# AirU_v2_0_wPOE.net
KiCad netlist of a schematic drawn in EAGLE
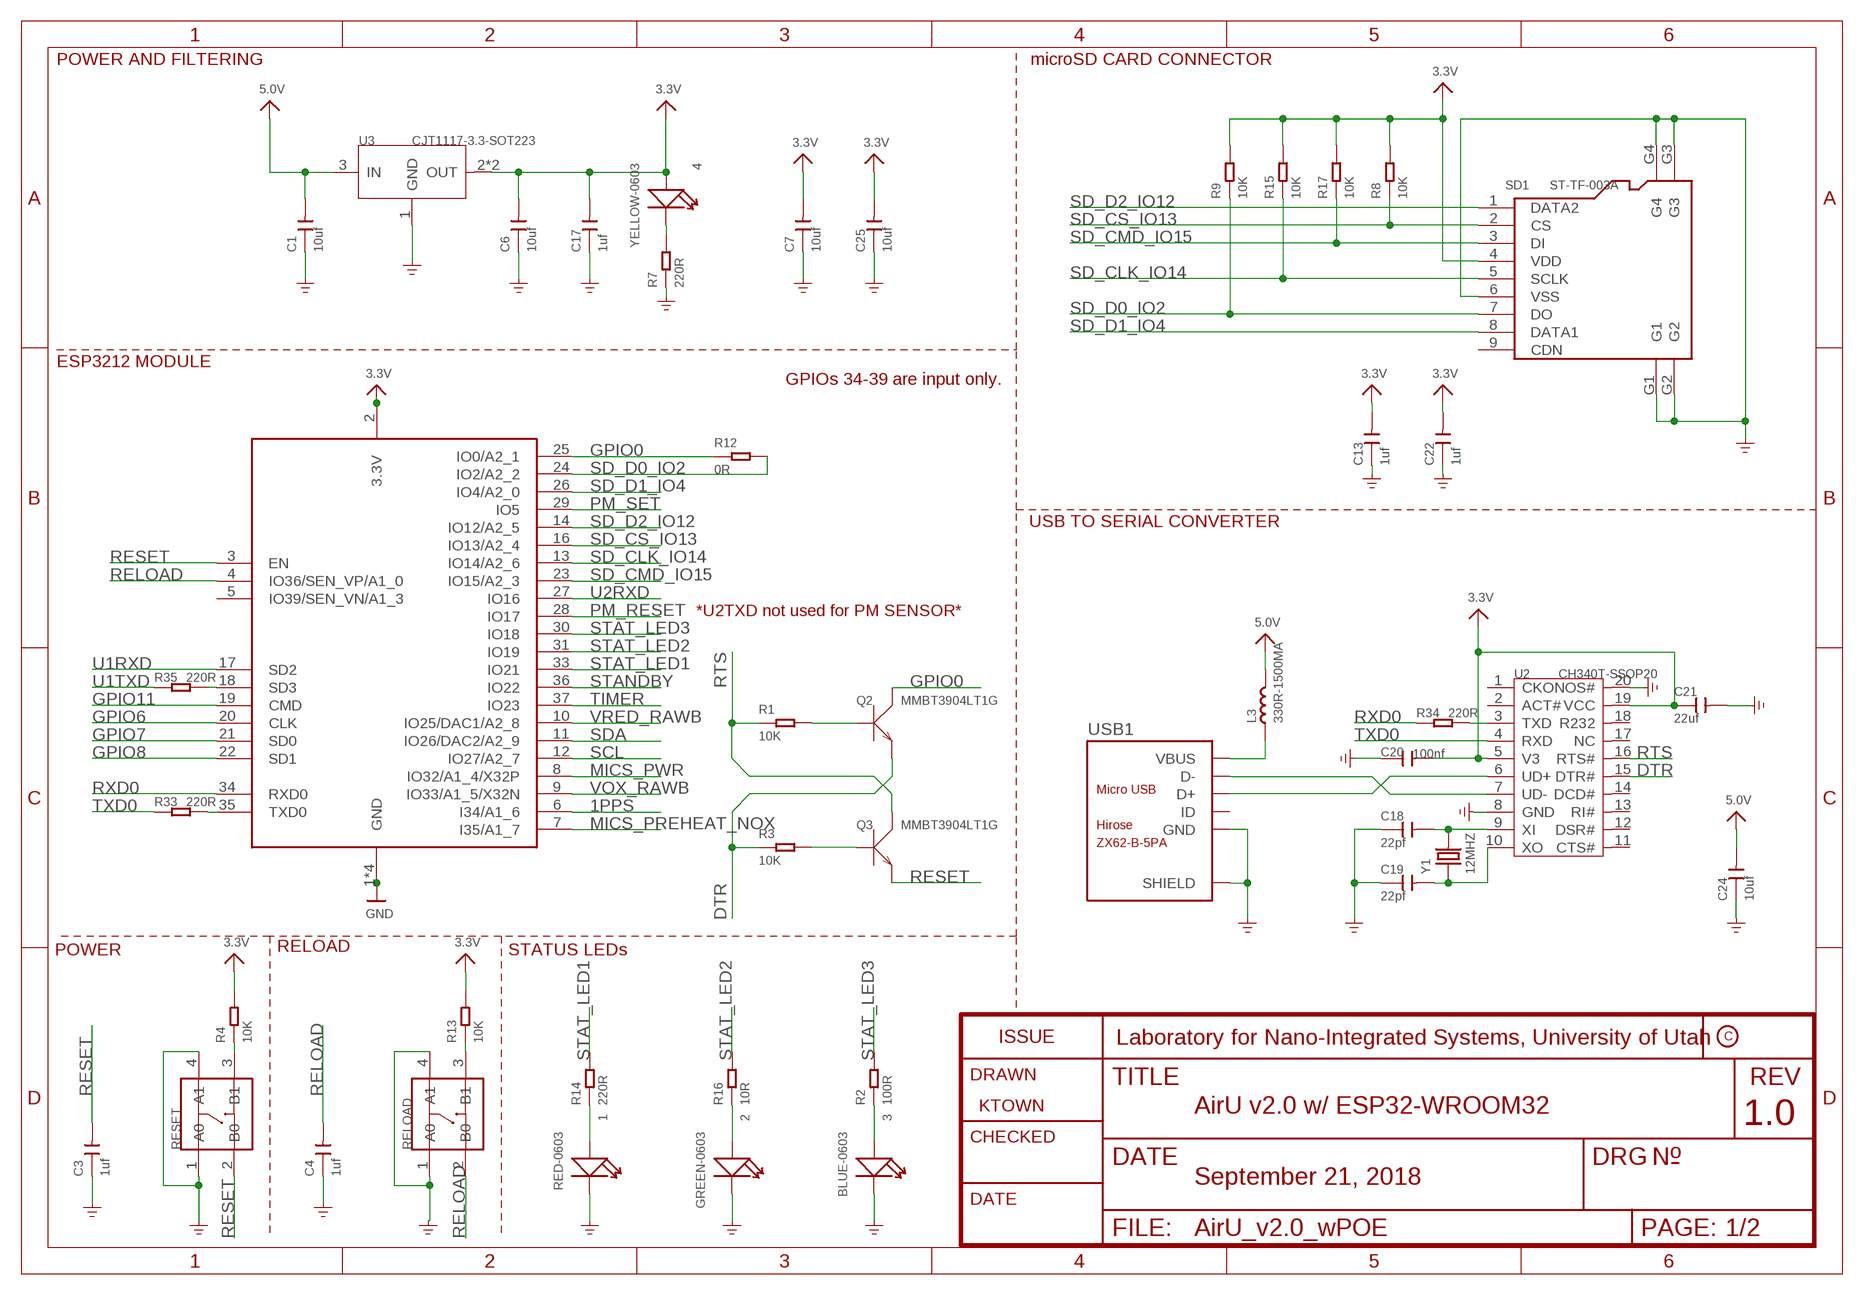
[diagram p0: schematic, sheet 1]
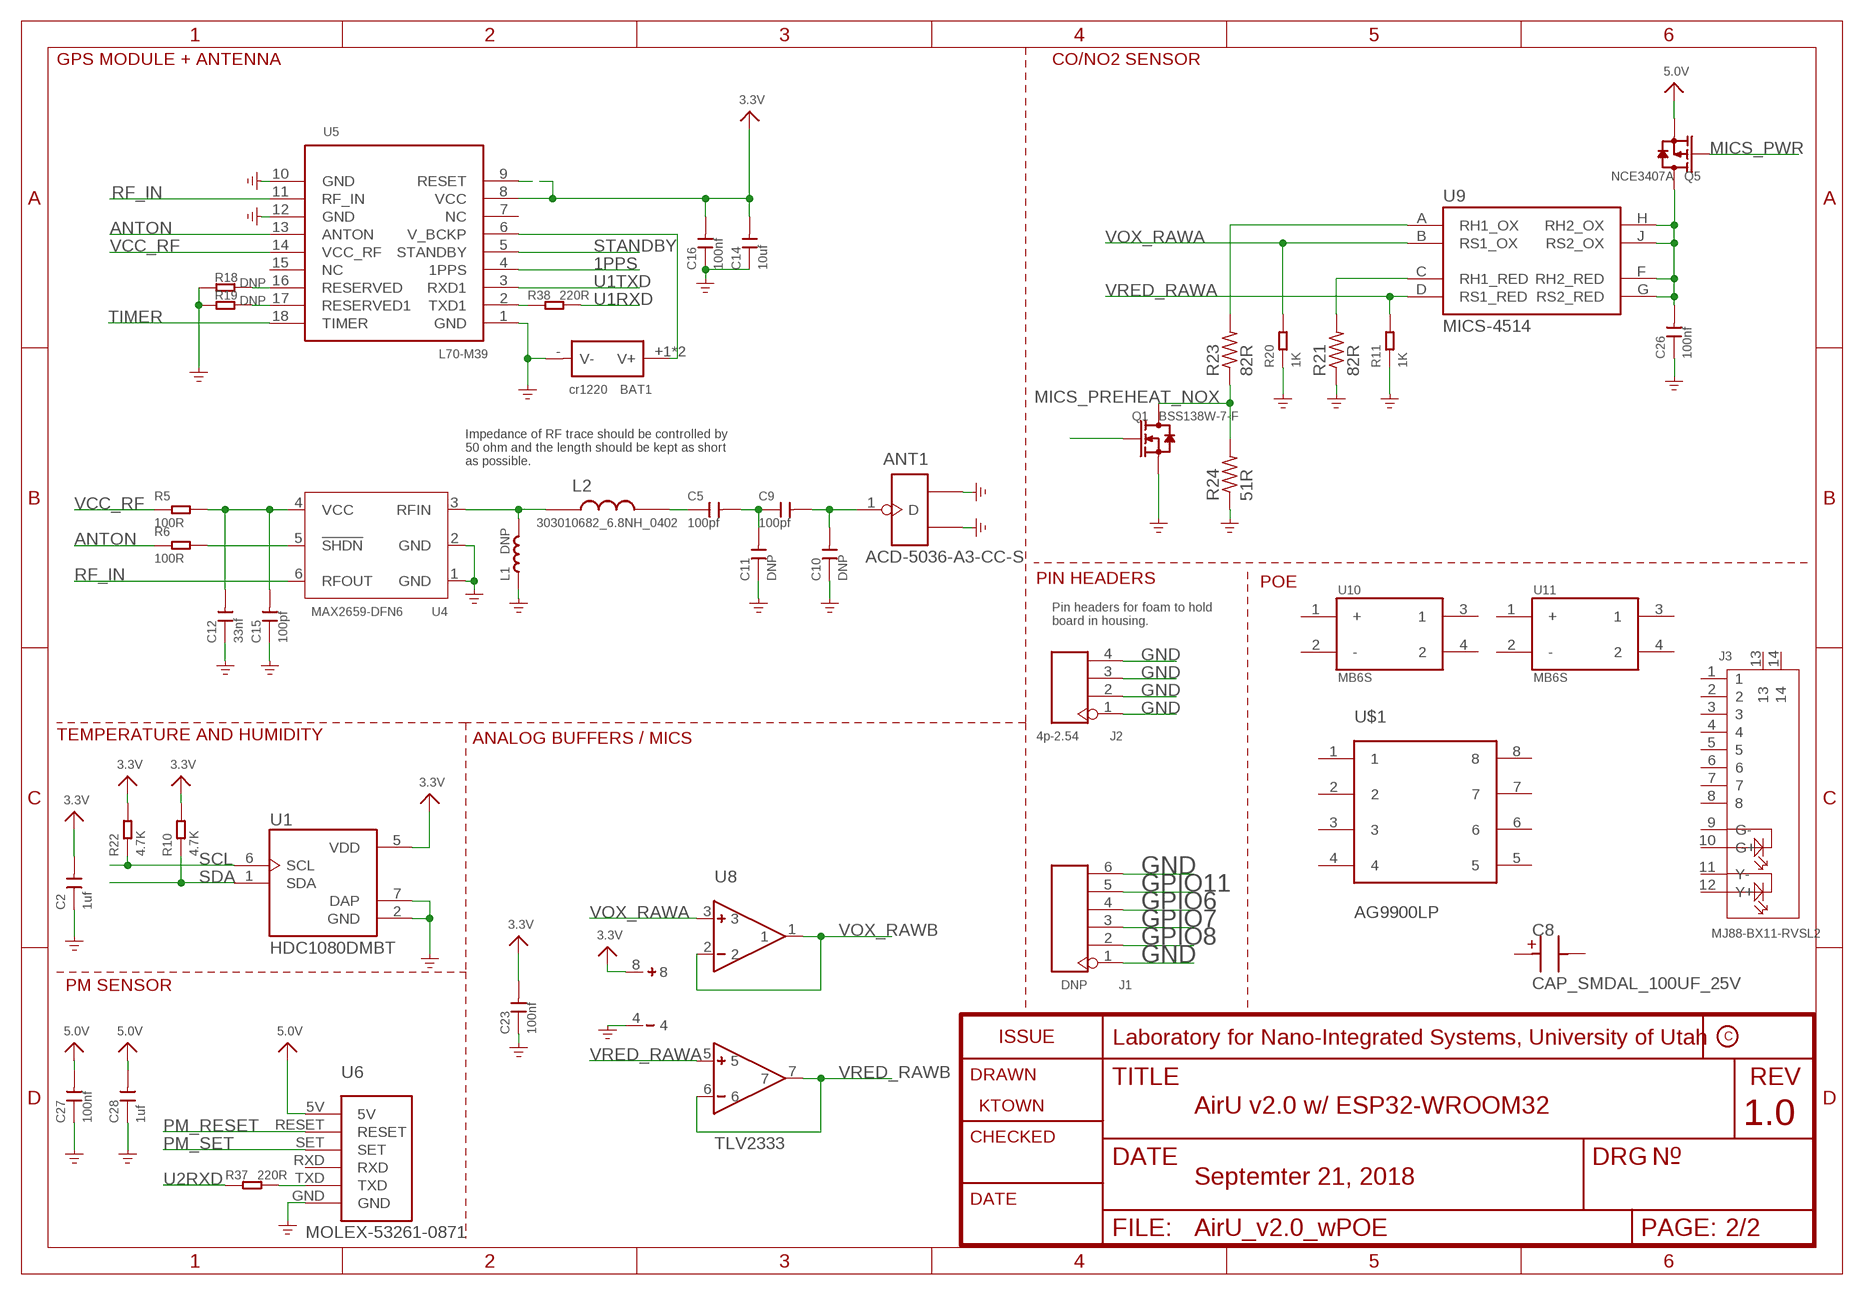
[diagram p1: schematic, sheet 2]

(export (version "E")
  (design (tool "Eeschema 10.0.6"))
  (components
    (comp (ref "1")
      (value "RED-0603")
      (footprint "eagle-import:LED-0603")
      (fields (field (name "MPN") "19-217-R6C-AL1M2VY-3T"))
      (libsource (lib "eagle-import") (part "LED-SMD-RED-DIFFUSED(0603)"))
    )
    (comp (ref "2")
      (value "GREEN-0603")
      (footprint "eagle-import:LED-0603")
      (fields (field (name "MPN") "19-217-G7C-AN1P2-3T"))
      (libsource (lib "eagle-import") (part "SMD-LED-CLEAR-GREEN(0603)"))
    )
    (comp (ref "3")
      (value "BLUE-0603")
      (footprint "eagle-import:LED-0603")
      (fields (field (name "MPN") "19-217-BHC-ZL1M2RY-3T"))
      (libsource (lib "eagle-import") (part "SMD-LED-CLEAR-BLUE(0603)"))
    )
    (comp (ref "4")
      (value "YELLOW-0603")
      (footprint "eagle-import:LED-0603")
      (fields (field (name "MPN") "19-217-Y5C-AM1N1VY-3T"))
      (libsource (lib "eagle-import") (part "SMD-LED-CLEAR-YELLOW(0603)"))
    )
    (comp (ref "C1")
      (value "10uf")
      (footprint "eagle-import:C0603")
      (fields (field (name "MPN") "CC0603KRX5R6BB106"))
      (libsource (lib "eagle-import") (part "CERAMIC-10UF-10V-10%-X5R(0603)"))
    )
    (comp (ref "C3")
      (value "1uf")
      (footprint "eagle-import:C0603")
      (fields (field (name "MPN") "CC0603KRX7R8BB105"))
      (libsource (lib "eagle-import") (part "CERAMIC-1UF-25V-10%-X7R(0603)"))
    )
    (comp (ref "C4")
      (value "1uf")
      (footprint "eagle-import:C0603")
      (fields (field (name "MPN") "CC0603KRX7R8BB105"))
      (libsource (lib "eagle-import") (part "CERAMIC-1UF-25V-10%-X7R(0603)"))
    )
    (comp (ref "C6")
      (value "10uf")
      (footprint "eagle-import:C0603")
      (fields (field (name "MPN") "CC0603KRX5R6BB106"))
      (libsource (lib "eagle-import") (part "CERAMIC-10UF-10V-10%-X5R(0603)"))
    )
    (comp (ref "C7")
      (value "10uf")
      (footprint "eagle-import:C0603")
      (fields (field (name "MPN") "CC0603KRX5R6BB106"))
      (libsource (lib "eagle-import") (part "CERAMIC-10UF-10V-10%-X5R(0603)"))
    )
    (comp (ref "C13")
      (value "1uf")
      (footprint "eagle-import:C0603")
      (fields (field (name "MPN") "CC0603KRX7R8BB105"))
      (libsource (lib "eagle-import") (part "CERAMIC-1UF-25V-10%-X7R(0603)"))
    )
    (comp (ref "C17")
      (value "1uf")
      (footprint "eagle-import:C0603")
      (fields (field (name "MPN") "CC0603KRX7R8BB105"))
      (libsource (lib "eagle-import") (part "CERAMIC-1UF-25V-10%-X7R(0603)"))
    )
    (comp (ref "C18")
      (value "22pf")
      (footprint "eagle-import:C0603")
      (fields (field (name "MPN") "CC0603JRNPO9BN220"))
      (libsource (lib "eagle-import") (part "CERAMIC-22PF-50V-5%-NPO(0603)"))
    )
    (comp (ref "C19")
      (value "22pf")
      (footprint "eagle-import:C0603")
      (fields (field (name "MPN") "CC0603JRNPO9BN220"))
      (libsource (lib "eagle-import") (part "CERAMIC-22PF-50V-5%-NPO(0603)"))
    )
    (comp (ref "C20")
      (value "100nf")
      (footprint "eagle-import:C0603")
      (fields (field (name "MPN") "CC0603KRX7R9BB104"))
      (libsource (lib "eagle-import") (part "CERAMIC-100NF-50V-10%-X7R(0603)"))
    )
    (comp (ref "C21")
      (value "22uf")
      (footprint "eagle-import:C0805")
      (fields (field (name "MPN") "CC0805MKX5R5BB226"))
      (libsource (lib "eagle-import") (part "CERAMIC-22UF-6.3V-20%-X5R(0805)"))
    )
    (comp (ref "C22")
      (value "1uf")
      (footprint "eagle-import:C0603")
      (fields (field (name "MPN") "CC0603KRX7R8BB105"))
      (libsource (lib "eagle-import") (part "CERAMIC-1UF-25V-10%-X7R(0603)"))
    )
    (comp (ref "C24")
      (value "10uf")
      (footprint "eagle-import:C0603")
      (fields (field (name "MPN") "CC0603KRX5R6BB106"))
      (libsource (lib "eagle-import") (part "CERAMIC-10UF-10V-10%-X5R(0603)"))
    )
    (comp (ref "C25")
      (value "10uf")
      (footprint "eagle-import:C0603")
      (fields (field (name "MPN") "CC0603KRX5R6BB106"))
      (libsource (lib "eagle-import") (part "CERAMIC-10UF-10V-10%-X5R(0603)"))
    )
    (comp (ref "L3")
      (value "330R-1500MA")
      (footprint "eagle-import:L0805")
      (fields (field (name "MPN") "BLM21PG331SN1D"))
      (libsource (lib "eagle-import") (part "SMD-FERRITE-BEAD-330R-1500MA(0805)'0805'"))
    )
    (comp (ref "Q2")
      (value "MMBT3904LT1G")
      (footprint "eagle-import:SOT-23")
      (libsource (lib "eagle-import") (part "SMD-TRANSISTORS-NPN-40V-200MA-MMBT3904LT1G(SOT-23)"))
    )
    (comp (ref "Q3")
      (value "MMBT3904LT1G")
      (footprint "eagle-import:SOT-23")
      (libsource (lib "eagle-import") (part "SMD-TRANSISTORS-NPN-40V-200MA-MMBT3904LT1G(SOT-23)"))
    )
    (comp (ref "R1")
      (value "10K")
      (footprint "eagle-import:R0603")
      (fields (field (name "MPN") "RC0603FR-0710KL"))
      (libsource (lib "eagle-import") (part "SMD-RES-10K-1%-1/10W(0603)"))
    )
    (comp (ref "R2")
      (value "100R")
      (footprint "eagle-import:R0603")
      (fields (field (name "MPN") "RC0603JR-07100RL"))
      (libsource (lib "eagle-import") (part "SMD-RES-100R-5%-1/10W(0603)"))
    )
    (comp (ref "R3")
      (value "10K")
      (footprint "eagle-import:R0603")
      (fields (field (name "MPN") "RC0603FR-0710KL"))
      (libsource (lib "eagle-import") (part "SMD-RES-10K-1%-1/10W(0603)"))
    )
    (comp (ref "R4")
      (value "10K")
      (footprint "eagle-import:R0603")
      (fields (field (name "MPN") "RC0603FR-0710KL"))
      (libsource (lib "eagle-import") (part "SMD-RES-10K-1%-1/10W(0603)"))
    )
    (comp (ref "R7")
      (value "220R")
      (footprint "eagle-import:R0603")
      (fields (field (name "MPN") "RC0603JR-07220RL"))
      (libsource (lib "eagle-import") (part "SMD-RES-220R-5%-1/10W(0603)"))
    )
    (comp (ref "R8")
      (value "10K")
      (footprint "eagle-import:R0603")
      (fields (field (name "MPN") "RC0603FR-0710KL"))
      (libsource (lib "eagle-import") (part "SMD-RES-10K-1%-1/10W(0603)"))
    )
    (comp (ref "R9")
      (value "10K")
      (footprint "eagle-import:R0603")
      (fields (field (name "MPN") "RC0603FR-0710KL"))
      (libsource (lib "eagle-import") (part "SMD-RES-10K-1%-1/10W(0603)"))
    )
    (comp (ref "R12")
      (value "0R")
      (footprint "eagle-import:R0603")
      (fields (field (name "MPN") "RC0603JR-070RL"))
      (libsource (lib "eagle-import") (part "SMD-RES-0R-5%-1/10W(0603)"))
    )
    (comp (ref "R13")
      (value "10K")
      (footprint "eagle-import:R0603")
      (fields (field (name "MPN") "RC0603FR-0710KL"))
      (libsource (lib "eagle-import") (part "SMD-RES-10K-1%-1/10W(0603)"))
    )
    (comp (ref "R14")
      (value "220R")
      (footprint "eagle-import:R0603")
      (fields (field (name "MPN") "RC0603JR-07220RL"))
      (libsource (lib "eagle-import") (part "SMD-RES-220R-5%-1/10W(0603)"))
    )
    (comp (ref "R15")
      (value "10K")
      (footprint "eagle-import:R0603")
      (fields (field (name "MPN") "RC0603FR-0710KL"))
      (libsource (lib "eagle-import") (part "SMD-RES-10K-1%-1/10W(0603)"))
    )
    (comp (ref "R16")
      (value "10R")
      (footprint "eagle-import:R0603")
      (fields (field (name "MPN") "RC0603JR-0710RL"))
      (libsource (lib "eagle-import") (part "SMD-RES-10R-5%-1/10W(0603)"))
    )
    (comp (ref "R17")
      (value "10K")
      (footprint "eagle-import:R0603")
      (fields (field (name "MPN") "RC0603FR-0710KL"))
      (libsource (lib "eagle-import") (part "SMD-RES-10K-1%-1/10W(0603)"))
    )
    (comp (ref "R33")
      (value "220R")
      (footprint "eagle-import:R0603")
      (fields (field (name "MPN") "RC0603JR-07220RL"))
      (libsource (lib "eagle-import") (part "SMD-RES-220R-5%-1/10W(0603)"))
    )
    (comp (ref "R34")
      (value "220R")
      (footprint "eagle-import:R0603")
      (fields (field (name "MPN") "RC0603JR-07220RL"))
      (libsource (lib "eagle-import") (part "SMD-RES-220R-5%-1/10W(0603)"))
    )
    (comp (ref "R35")
      (value "220R")
      (footprint "eagle-import:R0603")
      (fields (field (name "MPN") "RC0603JR-07220RL"))
      (libsource (lib "eagle-import") (part "SMD-RES-220R-5%-1/10W(0603)"))
    )
    (comp (ref "RELOAD")
      (value "DIP-SWITCH-TACTILE-SPST-NO/TS-1109(4P-D6.0MM)'TS-1109'")
      (footprint "eagle-import:SW4-6.0X6.0X5.0MM")
      (libsource (lib "eagle-import") (part "DIP-SWITCH-TACTILE-SPST-NO/TS-1109(4P-D6.0MM)'TS-1109'"))
    )
    (comp (ref "RESET")
      (value "DIP-SWITCH-TACTILE-SPST-NO/TS-1109(4P-D6.0MM)'TS-1109'")
      (footprint "eagle-import:SW4-6.0X6.0X5.0MM")
      (libsource (lib "eagle-import") (part "DIP-SWITCH-TACTILE-SPST-NO/TS-1109(4P-D6.0MM)'TS-1109'"))
    )
    (comp (ref "SD1")
      (value "ST-TF-003A")
      (footprint "eagle-import:MICRO-SD9+4P-SMD-16.1X14.5X1.85MM")
      (libsource (lib "eagle-import") (part "MICRO-SD-CARD-SOCKET-9P(ST-TF-003A)"))
    )
    (comp (ref "U2")
      (value "CH340T-SSOP20")
      (footprint "eagle-import:SSOP20-0.65-7.6X5.2MM")
      (fields (field (name "MPN") "CH340T"))
      (libsource (lib "eagle-import") (part "INTERFACE-CH340T(SSOP20)"))
    )
    (comp (ref "U3")
      (value "CJT1117-3.3-SOT223")
      (footprint "eagle-import:SOT-223")
      (fields (field (name "MPN") "CJT1117-3.3"))
      (libsource (lib "eagle-import") (part "PMIC-CJT1117-3.3(SOT223)"))
    )
    (comp (ref "U7")
      (value "ESP32_WROOM32_SKINNY")
      (footprint "eagle-import:WROOM32_SKINNY")
      (libsource (lib "eagle-import") (part "ESP32_WROOM32_SKINNY"))
    )
    (comp (ref "USB1")
      (value "ZX62-B-5PA")
      (footprint "eagle-import:MICRO-USB5+6P-SMD-0.65-AB")
      (libsource (lib "eagle-import") (part "MICRO-USB-SMD(ZX62-B-5PA)"))
    )
    (comp (ref "Y1")
      (value "12MHZ")
      (footprint "eagle-import:X2-SMD-5.0X3.2X1.3MM")
      (fields (field (name "MPN") "5032/2P"))
      (libsource (lib "eagle-import") (part "SMD-CRYSTAL-12MHZ-20PF-20PPM-40R(2P-5.0X3.2MM)"))
    )
    (comp (ref "ANT1")
      (value "ACD-5036-A3-CC-S")
      (footprint "eagle-import:ANT3-SMD-5.2X3.7X0.7MM")
      (libsource (lib "eagle-import") (part "ANTENNA-ACD5036"))
    )
    (comp (ref "BAT1")
      (value "cr1220")
      (footprint "eagle-import:BAT2P-13.5-CR1220")
      (libsource (lib "eagle-import") (part "DIP-BATTERY-CELL-HOLDER(1220)"))
    )
    (comp (ref "C2")
      (value "1uf")
      (footprint "eagle-import:C0603")
      (fields (field (name "MPN") "CC0603KRX7R8BB105"))
      (libsource (lib "eagle-import") (part "CERAMIC-1UF-25V-10%-X7R(0603)"))
    )
    (comp (ref "C5")
      (value "100pf")
      (footprint "eagle-import:C0603")
      (fields (field (name "MPN") "CC0603JRNPO9BN101"))
      (libsource (lib "eagle-import") (part "CERAMIC-100PF-50V-5%-NPO(0603)"))
    )
    (comp (ref "C8")
      (value "CAP_SMDAL_100UF_25V")
      (footprint "eagle-import:CAP_SMD_AL_D63")
      (libsource (lib "eagle-import") (part "CAP_SMDAL_100UF_25V"))
    )
    (comp (ref "C9")
      (value "100pf")
      (footprint "eagle-import:C0603")
      (fields (field (name "MPN") "CC0603JRNPO9BN101"))
      (libsource (lib "eagle-import") (part "CERAMIC-100PF-50V-5%-NPO(0603)"))
    )
    (comp (ref "C10")
      (value "DNP")
      (footprint "eagle-import:C0603")
      (fields (field (name "MPN") "CC0603JRNPO9BN101"))
      (libsource (lib "eagle-import") (part "CERAMIC-100PF-50V-5%-NPO(0603)"))
    )
    (comp (ref "C11")
      (value "DNP")
      (footprint "eagle-import:C0603")
      (fields (field (name "MPN") "CC0603JRNPO9BN101"))
      (libsource (lib "eagle-import") (part "CERAMIC-100PF-50V-5%-NPO(0603)"))
    )
    (comp (ref "C12")
      (value "33nf")
      (footprint "eagle-import:C0603")
      (fields (field (name "MPN") "CC0603KRX7R9BB333"))
      (libsource (lib "eagle-import") (part "CERAMIC-33NF-50V-10%-X7R(0603)"))
    )
    (comp (ref "C14")
      (value "10uf")
      (footprint "eagle-import:C0603")
      (fields (field (name "MPN") "CC0603KRX5R6BB106"))
      (libsource (lib "eagle-import") (part "CERAMIC-10UF-10V-10%-X5R(0603)"))
    )
    (comp (ref "C15")
      (value "100pf")
      (footprint "eagle-import:C0603")
      (fields (field (name "MPN") "CC0603JRNPO9BN101"))
      (libsource (lib "eagle-import") (part "CERAMIC-100PF-50V-5%-NPO(0603)"))
    )
    (comp (ref "C16")
      (value "100nf")
      (footprint "eagle-import:C0603")
      (fields (field (name "MPN") "CC0603KRX7R9BB104"))
      (libsource (lib "eagle-import") (part "CERAMIC-100NF-50V-10%-X7R(0603)"))
    )
    (comp (ref "C23")
      (value "100nf")
      (footprint "eagle-import:C0603")
      (fields (field (name "MPN") "CC0603KRX7R9BB104"))
      (libsource (lib "eagle-import") (part "CERAMIC-100NF-50V-10%-X7R(0603)"))
    )
    (comp (ref "C26")
      (value "100nf")
      (footprint "eagle-import:C0603")
      (fields (field (name "MPN") "CC0603KRX7R9BB104"))
      (libsource (lib "eagle-import") (part "CERAMIC-100NF-50V-10%-X7R(0603)"))
    )
    (comp (ref "C27")
      (value "100nf")
      (footprint "eagle-import:C0603")
      (fields (field (name "MPN") "CC0603KRX7R9BB104"))
      (libsource (lib "eagle-import") (part "CERAMIC-100NF-50V-10%-X7R(0603)"))
    )
    (comp (ref "C28")
      (value "1uf")
      (footprint "eagle-import:C0603")
      (fields (field (name "MPN") "CC0603KRX7R8BB105"))
      (libsource (lib "eagle-import") (part "CERAMIC-1UF-25V-10%-X7R(0603)"))
    )
    (comp (ref "J1")
      (value "DNP")
      (footprint "eagle-import:H6-2.54")
      (fields (field (name "MPN") "P125-1106A1BS116A1"))
      (libsource (lib "eagle-import") (part "DIP-BLACK-MALE-HEADER(6P-2.54)"))
    )
    (comp (ref "J2")
      (value "4p-2.54")
      (footprint "eagle-import:H4-2.54")
      (fields (field (name "MPN") "P125-1104A0BS116A1"))
      (libsource (lib "eagle-import") (part "DIP-BLACK-MALE-HEADER-VERT(4P-2.54)"))
    )
    (comp (ref "J3")
      (value "MJ88-BX11-RVSL2")
      (footprint "eagle-import:RJ45-12+2P-16.3X15.4X11.5MM-IN")
      (libsource (lib "eagle-import") (part "RJ45-MJ88-BX11-RVSL2"))
    )
    (comp (ref "L1")
      (value "DNP")
      (footprint "eagle-import:L0201")
      (libsource (lib "eagle-import") (part "INDUCTOR/FERRITE-BEAD-0201"))
    )
    (comp (ref "L2")
      (value "303010682_6.8NH_0402")
      (footprint "eagle-import:L0402")
      (libsource (lib "eagle-import") (part "303010682_6.8NH_0402"))
    )
    (comp (ref "Q1")
      (value "BSS138W-7-F")
      (footprint "eagle-import:SOT-23")
      (libsource (lib "eagle-import") (part "SMD-MOSFET-N-CH-50V-200MA-BSS138W-7-F(SOT-23)"))
    )
    (comp (ref "Q5")
      (value "NCE3407A")
      (footprint "eagle-import:SOT-23")
      (libsource (lib "eagle-import") (part "SMD-MOSFET-P-CH-VDC=30V-ID=4.3A-NCE3407A(SOT-23)"))
    )
    (comp (ref "R5")
      (value "100R")
      (footprint "eagle-import:R0603")
      (fields (field (name "MPN") "RC0603JR-07100RL"))
      (libsource (lib "eagle-import") (part "SMD-RES-100R-5%-1/10W(0603)"))
    )
    (comp (ref "R6")
      (value "100R")
      (footprint "eagle-import:R0603")
      (fields (field (name "MPN") "RC0603JR-07100RL"))
      (libsource (lib "eagle-import") (part "SMD-RES-100R-5%-1/10W(0603)"))
    )
    (comp (ref "R10")
      (value "4.7K")
      (footprint "eagle-import:R0603")
      (fields (field (name "MPN") "RC0603JR-074K7L"))
      (libsource (lib "eagle-import") (part "SMD-RES-4.7K-5%-1/10W(0603)"))
    )
    (comp (ref "R11")
      (value "1K")
      (footprint "eagle-import:R0603")
      (fields (field (name "MPN") "RC0603FR-071KL"))
      (libsource (lib "eagle-import") (part "SMD-RES-1K-1%-1/10W(0603)"))
    )
    (comp (ref "R18")
      (value "DNP")
      (footprint "eagle-import:R0603")
      (fields (field (name "MPN") "RC0603FR-0710KL"))
      (libsource (lib "eagle-import") (part "SMD-RES-10K-1%-1/10W(0603)"))
    )
    (comp (ref "R19")
      (value "DNP")
      (footprint "eagle-import:R0603")
      (fields (field (name "MPN") "RC0603FR-0710KL"))
      (libsource (lib "eagle-import") (part "SMD-RES-10K-1%-1/10W(0603)"))
    )
    (comp (ref "R20")
      (value "1K")
      (footprint "eagle-import:R0603")
      (fields (field (name "MPN") "RC0603FR-071KL"))
      (libsource (lib "eagle-import") (part "SMD-RES-1K-1%-1/10W(0603)"))
    )
    (comp (ref "R21")
      (value "82R")
      (footprint "eagle-import:R0603")
      (libsource (lib "eagle-import") (part "R-US_R0603"))
    )
    (comp (ref "R22")
      (value "4.7K")
      (footprint "eagle-import:R0603")
      (fields (field (name "MPN") "RC0603JR-074K7L"))
      (libsource (lib "eagle-import") (part "SMD-RES-4.7K-5%-1/10W(0603)"))
    )
    (comp (ref "R23")
      (value "82R")
      (footprint "eagle-import:R0603")
      (libsource (lib "eagle-import") (part "R-US_R0603"))
    )
    (comp (ref "R24")
      (value "51R")
      (footprint "eagle-import:R0603")
      (libsource (lib "eagle-import") (part "R-US_R0603"))
    )
    (comp (ref "R37")
      (value "220R")
      (footprint "eagle-import:R0603")
      (fields (field (name "MPN") "RC0603JR-07220RL"))
      (libsource (lib "eagle-import") (part "SMD-RES-220R-5%-1/10W(0603)"))
    )
    (comp (ref "R38")
      (value "220R")
      (footprint "eagle-import:R0603")
      (fields (field (name "MPN") "RC0603JR-07220RL"))
      (libsource (lib "eagle-import") (part "SMD-RES-220R-5%-1/10W(0603)"))
    )
    (comp (ref "U$1")
      (value "AG9900LP")
      (footprint "eagle-import:AG9900LP")
      (libsource (lib "eagle-import") (part "AG9900LP"))
    )
    (comp (ref "U1")
      (value "HDC1080DMBT")
      (footprint "eagle-import:SON100P300X300X80-7N")
      (fields (field (name "DIGI-KEY_PART_NUMBER") "296-43864-1-ND") (field (name "MF") "Texas Instruments"))
      (libsource (lib "eagle-import") (part "HDC1080DMBT"))
    )
    (comp (ref "U4")
      (value "MAX2659-DFN6")
      (footprint "eagle-import:DFN6-0.5-1.5X1.2X0.72MM")
      (fields (field (name "MPN") "MAX2659"))
      (libsource (lib "eagle-import") (part "AMPLIFIER-MAX2659"))
    )
    (comp (ref "U5")
      (value "L70-M39")
      (footprint "eagle-import:LGA18-1.1-9.7X10.1X2.5MM")
      (fields (field (name "MPN") "L70"))
      (libsource (lib "eagle-import") (part "MOUDLE-GPS-L70-HARDWARE"))
    )
    (comp (ref "U6")
      (value "MOLEX-53261-0871")
      (footprint "eagle-import:MOLEX-53261-0871")
      (libsource (lib "eagle-import") (part "MOLEX-53261-0871"))
    )
    (comp (ref "U8")
      (value "TLV2333")
      (footprint "eagle-import:TLV2333")
      (libsource (lib "eagle-import") (part "TLV2333"))
    )
    (comp (ref "U9")
      (value "MICS-4514")
      (footprint "eagle-import:MICS_10-SMD")
      (fields (field (name "MF") "Amphenol"))
      (libsource (lib "eagle-import") (part "MICS-4514"))
    )
    (comp (ref "U10")
      (value "MB6S")
      (footprint "eagle-import:SOIC245P670X270-4N")
      (fields (field (name "MF") "ON Semiconductor"))
      (libsource (lib "eagle-import") (part "MB6S"))
    )
    (comp (ref "U11")
      (value "MB6S")
      (footprint "eagle-import:SOIC245P670X270-4N")
      (fields (field (name "MF") "ON Semiconductor"))
      (libsource (lib "eagle-import") (part "MB6S"))
    )
  )
  (nets
    (net (code "1") (name "1PPS") (class "Default")
      (node (ref "U5") (pin "4") (pinfunction "1PPS_4") (pintype "bidirectional"))
      (node (ref "U7") (pin "6") (pinfunction "I34/A1_6_6") (pintype "bidirectional"))
    )
    (net (code "2") (name "3.3V") (class "Default")
      (node (ref "4") (pin "+") (pinfunction "+_+") (pintype "passive"))
      (node (ref "C13") (pin "2") (pinfunction "2_2") (pintype "passive"))
      (node (ref "C14") (pin "2") (pinfunction "2_2") (pintype "passive"))
      (node (ref "C16") (pin "2") (pinfunction "2_2") (pintype "passive"))
      (node (ref "C17") (pin "2") (pinfunction "2_2") (pintype "passive"))
      (node (ref "C2") (pin "2") (pinfunction "2_2") (pintype "passive"))
      (node (ref "C20") (pin "2") (pinfunction "2_2") (pintype "passive"))
      (node (ref "C21") (pin "1") (pinfunction "1_1") (pintype "passive"))
      (node (ref "C22") (pin "2") (pinfunction "2_2") (pintype "passive"))
      (node (ref "C23") (pin "2") (pinfunction "2_2") (pintype "passive"))
      (node (ref "C25") (pin "2") (pinfunction "2_2") (pintype "passive"))
      (node (ref "C6") (pin "2") (pinfunction "2_2") (pintype "passive"))
      (node (ref "C7") (pin "2") (pinfunction "2_2") (pintype "passive"))
      (node (ref "R10") (pin "2") (pinfunction "2_2") (pintype "passive"))
      (node (ref "R13") (pin "2") (pinfunction "2_2") (pintype "passive"))
      (node (ref "R15") (pin "2") (pinfunction "2_2") (pintype "passive"))
      (node (ref "R17") (pin "2") (pinfunction "2_2") (pintype "passive"))
      (node (ref "R22") (pin "2") (pinfunction "2_2") (pintype "passive"))
      (node (ref "R4") (pin "2") (pinfunction "2_2") (pintype "passive"))
      (node (ref "R8") (pin "2") (pinfunction "2_2") (pintype "passive"))
      (node (ref "R9") (pin "2") (pinfunction "2_2") (pintype "passive"))
      (node (ref "SD1") (pin "4") (pinfunction "VDD_4") (pintype "bidirectional"))
      (node (ref "U1") (pin "5") (pinfunction "VDD_5") (pintype "power_in"))
      (node (ref "U2") (pin "19") (pinfunction "VCC_19") (pintype "power_in"))
      (node (ref "U2") (pin "5") (pinfunction "V3_5") (pintype "power_in"))
      (node (ref "U3") (pin "2") (pinfunction "OUT_2") (pintype "bidirectional"))
      (node (ref "U3") (pin "TER") (pinfunction "OUT_TER") (pintype "bidirectional"))
      (node (ref "U5") (pin "8") (pinfunction "VCC_8") (pintype "power_in"))
      (node (ref "U5") (pin "9") (pinfunction "RESET_9") (pintype "bidirectional"))
      (node (ref "U7") (pin "2") (pinfunction "3.3V_2") (pintype "passive"))
      (node (ref "U8") (pin "8") (pinfunction "8_8") (pintype "bidirectional"))
    )
    (net (code "3") (name "5.0V") (class "Default")
      (node (ref "C1") (pin "2") (pinfunction "2_2") (pintype "passive"))
      (node (ref "C24") (pin "2") (pinfunction "2_2") (pintype "passive"))
      (node (ref "C27") (pin "2") (pinfunction "2_2") (pintype "passive"))
      (node (ref "C28") (pin "2") (pinfunction "2_2") (pintype "passive"))
      (node (ref "L3") (pin "2") (pinfunction "2_2") (pintype "passive"))
      (node (ref "Q5") (pin "2") (pinfunction "S_2") (pintype "passive"))
      (node (ref "U3") (pin "3") (pinfunction "IN_3") (pintype "bidirectional"))
      (node (ref "U6") (pin "5V") (pinfunction "5V_5V") (pintype "bidirectional"))
    )
    (net (code "4") (name "ANTON") (class "Default")
      (node (ref "R6") (pin "1") (pinfunction "1_1") (pintype "passive"))
      (node (ref "U5") (pin "13") (pinfunction "ANTON_13") (pintype "bidirectional"))
    )
    (net (code "5") (name "DTR") (class "Default")
      (node (ref "Q2") (pin "2") (pinfunction "E_2") (pintype "passive"))
      (node (ref "R3") (pin "1") (pinfunction "1_1") (pintype "passive"))
      (node (ref "U2") (pin "15") (pinfunction "DTR#_15") (pintype "output"))
    )
    (net (code "6") (name "GND") (class "Default")
      (node (ref "1") (pin "-") (pinfunction "-_-") (pintype "passive"))
      (node (ref "2") (pin "-") (pinfunction "-_-") (pintype "passive"))
      (node (ref "3") (pin "-") (pinfunction "-_-") (pintype "passive"))
      (node (ref "ANT1") (pin "2") (pinfunction "GND1_2") (pintype "bidirectional"))
      (node (ref "ANT1") (pin "3") (pinfunction "GND2_3") (pintype "bidirectional"))
      (node (ref "BAT1") (pin "-") (pinfunction "V-_-") (pintype "bidirectional"))
      (node (ref "C1") (pin "1") (pinfunction "1_1") (pintype "passive"))
      (node (ref "C10") (pin "1") (pinfunction "1_1") (pintype "passive"))
      (node (ref "C11") (pin "1") (pinfunction "1_1") (pintype "passive"))
      (node (ref "C12") (pin "1") (pinfunction "1_1") (pintype "passive"))
      (node (ref "C13") (pin "1") (pinfunction "1_1") (pintype "passive"))
      (node (ref "C14") (pin "1") (pinfunction "1_1") (pintype "passive"))
      (node (ref "C15") (pin "1") (pinfunction "1_1") (pintype "passive"))
      (node (ref "C16") (pin "1") (pinfunction "1_1") (pintype "passive"))
      (node (ref "C17") (pin "1") (pinfunction "1_1") (pintype "passive"))
      (node (ref "C18") (pin "1") (pinfunction "1_1") (pintype "passive"))
      (node (ref "C19") (pin "1") (pinfunction "1_1") (pintype "passive"))
      (node (ref "C2") (pin "1") (pinfunction "1_1") (pintype "passive"))
      (node (ref "C20") (pin "1") (pinfunction "1_1") (pintype "passive"))
      (node (ref "C21") (pin "2") (pinfunction "2_2") (pintype "passive"))
      (node (ref "C22") (pin "1") (pinfunction "1_1") (pintype "passive"))
      (node (ref "C23") (pin "1") (pinfunction "1_1") (pintype "passive"))
      (node (ref "C24") (pin "1") (pinfunction "1_1") (pintype "passive"))
      (node (ref "C25") (pin "1") (pinfunction "1_1") (pintype "passive"))
      (node (ref "C26") (pin "1") (pinfunction "1_1") (pintype "passive"))
      (node (ref "C27") (pin "1") (pinfunction "1_1") (pintype "passive"))
      (node (ref "C28") (pin "1") (pinfunction "1_1") (pintype "passive"))
      (node (ref "C3") (pin "1") (pinfunction "1_1") (pintype "passive"))
      (node (ref "C4") (pin "1") (pinfunction "1_1") (pintype "passive"))
      (node (ref "C6") (pin "1") (pinfunction "1_1") (pintype "passive"))
      (node (ref "C7") (pin "1") (pinfunction "1_1") (pintype "passive"))
      (node (ref "J1") (pin "1") (pinfunction "1_1") (pintype "bidirectional"))
      (node (ref "J1") (pin "6") (pinfunction "6_6") (pintype "bidirectional"))
      (node (ref "J2") (pin "1") (pinfunction "P$1_1") (pintype "bidirectional"))
      (node (ref "J2") (pin "2") (pinfunction "P$2_2") (pintype "bidirectional"))
      (node (ref "J2") (pin "3") (pinfunction "P$3_3") (pintype "bidirectional"))
      (node (ref "J2") (pin "4") (pinfunction "P$4_4") (pintype "bidirectional"))
      (node (ref "L1") (pin "1") (pinfunction "1_1") (pintype "passive"))
      (node (ref "Q1") (pin "2") (pinfunction "S_2") (pintype "passive"))
      (node (ref "R11") (pin "1") (pinfunction "1_1") (pintype "passive"))
      (node (ref "R18") (pin "1") (pinfunction "1_1") (pintype "passive"))
      (node (ref "R19") (pin "1") (pinfunction "1_1") (pintype "passive"))
      (node (ref "R20") (pin "1") (pinfunction "1_1") (pintype "passive"))
      (node (ref "R21") (pin "1") (pinfunction "1_1") (pintype "passive"))
      (node (ref "R24") (pin "1") (pinfunction "1_1") (pintype "passive"))
      (node (ref "R7") (pin "1") (pinfunction "1_1") (pintype "passive"))
      (node (ref "RELOAD") (pin "1") (pinfunction "A0_1") (pintype "bidirectional"))
      (node (ref "RELOAD") (pin "4") (pinfunction "A1_4") (pintype "bidirectional"))
      (node (ref "RESET") (pin "1") (pinfunction "A0_1") (pintype "bidirectional"))
      (node (ref "RESET") (pin "4") (pinfunction "A1_4") (pintype "bidirectional"))
      (node (ref "SD1") (pin "6") (pinfunction "VSS_6") (pintype "bidirectional"))
      (node (ref "SD1") (pin "G1") (pinfunction "G1_G1") (pintype "bidirectional"))
      (node (ref "SD1") (pin "G2") (pinfunction "G2_G2") (pintype "bidirectional"))
      (node (ref "SD1") (pin "G3") (pinfunction "G3_G3") (pintype "bidirectional"))
      (node (ref "SD1") (pin "G4") (pinfunction "G4_G4") (pintype "bidirectional"))
      (node (ref "U1") (pin "2") (pinfunction "GND_2") (pintype "power_in"))
      (node (ref "U1") (pin "7") (pinfunction "DAP_7") (pintype "power_in"))
      (node (ref "U2") (pin "20") (pinfunction "NOS#_20") (pintype "power_in"))
      (node (ref "U2") (pin "8") (pinfunction "GND_8") (pintype "power_in"))
      (node (ref "U3") (pin "1") (pinfunction "GND_1") (pintype "bidirectional"))
      (node (ref "U4") (pin "1") (pinfunction "GND_1") (pintype "power_in"))
      (node (ref "U4") (pin "2") (pinfunction "GND_2") (pintype "power_in"))
      (node (ref "U5") (pin "1") (pinfunction "GND_1") (pintype "power_in"))
      (node (ref "U5") (pin "10") (pinfunction "GND_10") (pintype "power_in"))
      (node (ref "U5") (pin "12") (pinfunction "GND_12") (pintype "bidirectional"))
      (node (ref "U6") (pin "GND") (pinfunction "GND_GND") (pintype "bidirectional"))
      (node (ref "U7") (pin "1") (pinfunction "GND_1") (pintype "passive"))
      (node (ref "U7") (pin "15") (pinfunction "GND_15") (pintype "passive"))
      (node (ref "U7") (pin "38") (pinfunction "GND_38") (pintype "passive"))
      (node (ref "U7") (pin "P$1") (pinfunction "GND_P$1") (pintype "passive"))
      (node (ref "U8") (pin "4") (pinfunction "4_4") (pintype "bidirectional"))
      (node (ref "USB1") (pin "5") (pinfunction "GND_5") (pintype "power_in"))
      (node (ref "USB1") (pin "P1") (pinfunction "SHIELD_P1") (pintype "power_in"))
      (node (ref "USB1") (pin "P2") (pinfunction "SHIELD_P2") (pintype "power_in"))
      (node (ref "USB1") (pin "P3_1") (pinfunction "SHIELD_P3_1") (pintype "power_in"))
      (node (ref "USB1") (pin "P3_2") (pinfunction "SHIELD_P3_2") (pintype "power_in"))
      (node (ref "USB1") (pin "P3_3") (pinfunction "SHIELD_P3_3") (pintype "power_in"))
      (node (ref "USB1") (pin "P4_1") (pinfunction "SHIELD_P4_1") (pintype "power_in"))
      (node (ref "USB1") (pin "P4_2") (pinfunction "SHIELD_P4_2") (pintype "power_in"))
      (node (ref "USB1") (pin "P4_3") (pinfunction "SHIELD_P4_3") (pintype "power_in"))
      (node (ref "USB1") (pin "P5") (pinfunction "SHIELD_P5") (pintype "power_in"))
      (node (ref "USB1") (pin "P6") (pinfunction "SHIELD_P6") (pintype "power_in"))
    )
    (net (code "7") (name "GPIO0") (class "Default")
      (node (ref "Q2") (pin "3") (pinfunction "C_3") (pintype "passive"))
      (node (ref "R12") (pin "1") (pinfunction "1_1") (pintype "passive"))
      (node (ref "U7") (pin "25") (pinfunction "IO0/A2_1_25") (pintype "bidirectional"))
    )
    (net (code "8") (name "GPIO6") (class "Default")
      (node (ref "J1") (pin "4") (pinfunction "4_4") (pintype "bidirectional"))
      (node (ref "U7") (pin "20") (pinfunction "CLK_20") (pintype "bidirectional"))
    )
    (net (code "9") (name "GPIO7") (class "Default")
      (node (ref "J1") (pin "3") (pinfunction "3_3") (pintype "bidirectional"))
      (node (ref "U7") (pin "21") (pinfunction "SD0_21") (pintype "bidirectional"))
    )
    (net (code "10") (name "GPIO8") (class "Default")
      (node (ref "J1") (pin "2") (pinfunction "2_2") (pintype "bidirectional"))
      (node (ref "U7") (pin "22") (pinfunction "SD1_22") (pintype "bidirectional"))
    )
    (net (code "11") (name "GPIO11") (class "Default")
      (node (ref "J1") (pin "5") (pinfunction "5_5") (pintype "bidirectional"))
      (node (ref "U7") (pin "19") (pinfunction "CMD_19") (pintype "bidirectional"))
    )
    (net (code "12") (name "MICS_PREHEAT_NOX") (class "Default")
      (node (ref "Q1") (pin "1") (pinfunction "G_1") (pintype "passive"))
      (node (ref "U7") (pin "7") (pinfunction "I35/A1_7_7") (pintype "bidirectional"))
    )
    (net (code "13") (name "MICS_PWR") (class "Default")
      (node (ref "Q5") (pin "1") (pinfunction "G_1") (pintype "passive"))
      (node (ref "U7") (pin "8") (pinfunction "IO32/A1_4/X32P_8") (pintype "bidirectional"))
    )
    (net (code "14") (name "Net-(1-Pad+)") (class "Default")
      (node (ref "1") (pin "+") (pinfunction "+_+") (pintype "passive"))
      (node (ref "R14") (pin "1") (pinfunction "1_1") (pintype "passive"))
    )
    (net (code "15") (name "Net-(2-Pad+)") (class "Default")
      (node (ref "2") (pin "+") (pinfunction "+_+") (pintype "passive"))
      (node (ref "R16") (pin "1") (pinfunction "1_1") (pintype "passive"))
    )
    (net (code "16") (name "Net-(3-Pad+)") (class "Default")
      (node (ref "3") (pin "+") (pinfunction "+_+") (pintype "passive"))
      (node (ref "R2") (pin "1") (pinfunction "1_1") (pintype "passive"))
    )
    (net (code "17") (name "Net-(4-Pad-)") (class "Default")
      (node (ref "4") (pin "-") (pinfunction "-_-") (pintype "passive"))
      (node (ref "R7") (pin "2") (pinfunction "2_2") (pintype "passive"))
    )
    (net (code "18") (name "Net-(ANT1-D)") (class "Default")
      (node (ref "ANT1") (pin "1") (pinfunction "D_1") (pintype "bidirectional"))
      (node (ref "C10") (pin "2") (pinfunction "2_2") (pintype "passive"))
      (node (ref "C9") (pin "2") (pinfunction "2_2") (pintype "passive"))
    )
    (net (code "19") (name "Net-(C5-Pad1)") (class "Default")
      (node (ref "C5") (pin "1") (pinfunction "1_1") (pintype "passive"))
      (node (ref "L2") (pin "P$2") (pinfunction "P$2_P$2") (pintype "passive"))
    )
    (net (code "20") (name "Net-(C11-Pad2)") (class "Default")
      (node (ref "C11") (pin "2") (pinfunction "2_2") (pintype "passive"))
      (node (ref "C5") (pin "2") (pinfunction "2_2") (pintype "passive"))
      (node (ref "C9") (pin "1") (pinfunction "1_1") (pintype "passive"))
    )
    (net (code "21") (name "Net-(Q1-D)") (class "Default")
      (node (ref "Q1") (pin "3") (pinfunction "D_3") (pintype "passive"))
      (node (ref "R23") (pin "1") (pinfunction "1_1") (pintype "passive"))
      (node (ref "R24") (pin "2") (pinfunction "2_2") (pintype "passive"))
    )
    (net (code "22") (name "Net-(Q2-B)") (class "Default")
      (node (ref "Q2") (pin "1") (pinfunction "B_1") (pintype "passive"))
      (node (ref "R1") (pin "2") (pinfunction "2_2") (pintype "passive"))
    )
    (net (code "23") (name "Net-(Q3-B)") (class "Default")
      (node (ref "Q3") (pin "1") (pinfunction "B_1") (pintype "passive"))
      (node (ref "R3") (pin "2") (pinfunction "2_2") (pintype "passive"))
    )
    (net (code "24") (name "Net-(Q5-D)") (class "Default")
      (node (ref "C26") (pin "2") (pinfunction "2_2") (pintype "passive"))
      (node (ref "Q5") (pin "3") (pinfunction "D_3") (pintype "passive"))
      (node (ref "U9") (pin "F") (pinfunction "RH2_RED_F") (pintype "bidirectional"))
      (node (ref "U9") (pin "G") (pinfunction "RS2_RED_G") (pintype "bidirectional"))
      (node (ref "U9") (pin "H") (pinfunction "RH2_OX_H") (pintype "bidirectional"))
      (node (ref "U9") (pin "J") (pinfunction "RS2_OX_J") (pintype "bidirectional"))
    )
    (net (code "25") (name "Net-(R37-Pad2)") (class "Default")
      (node (ref "R37") (pin "2") (pinfunction "2_2") (pintype "passive"))
      (node (ref "U6") (pin "TXD") (pinfunction "TXD_TXD") (pintype "bidirectional"))
    )
    (net (code "26") (name "Net-(RELOAD-B1)") (class "Default")
      (node (ref "R13") (pin "1") (pinfunction "1_1") (pintype "passive"))
      (node (ref "RELOAD") (pin "3") (pinfunction "B1_3") (pintype "bidirectional"))
    )
    (net (code "27") (name "Net-(RESET-B1)") (class "Default")
      (node (ref "R4") (pin "1") (pinfunction "1_1") (pintype "passive"))
      (node (ref "RESET") (pin "3") (pinfunction "B1_3") (pintype "bidirectional"))
    )
    (net (code "28") (name "Net-(U2-TXD)") (class "Default")
      (node (ref "R34") (pin "2") (pinfunction "2_2") (pintype "passive"))
      (node (ref "U2") (pin "3") (pinfunction "TXD_3") (pintype "output"))
    )
    (net (code "29") (name "Net-(U2-UD+)") (class "Default")
      (node (ref "U2") (pin "6") (pinfunction "UD+_6") (pintype "bidirectional"))
      (node (ref "USB1") (pin "3") (pinfunction "D+_3") (pintype "bidirectional"))
    )
    (net (code "30") (name "Net-(U2-UD-)") (class "Default")
      (node (ref "U2") (pin "7") (pinfunction "UD-_7") (pintype "bidirectional"))
      (node (ref "USB1") (pin "2") (pinfunction "D-_2") (pintype "bidirectional"))
    )
    (net (code "31") (name "Net-(U2-XI)") (class "Default")
      (node (ref "C18") (pin "2") (pinfunction "2_2") (pintype "passive"))
      (node (ref "U2") (pin "9") (pinfunction "XI_9") (pintype "input"))
      (node (ref "Y1") (pin "2") (pinfunction "2_2") (pintype "passive"))
    )
    (net (code "32") (name "Net-(U2-XO)") (class "Default")
      (node (ref "C19") (pin "2") (pinfunction "2_2") (pintype "passive"))
      (node (ref "U2") (pin "10") (pinfunction "XO_10") (pintype "output"))
      (node (ref "Y1") (pin "1") (pinfunction "1_1") (pintype "passive"))
    )
    (net (code "33") (name "Net-(U4-RFIN)") (class "Default")
      (node (ref "L1") (pin "2") (pinfunction "2_2") (pintype "passive"))
      (node (ref "L2") (pin "P$1") (pinfunction "P$1_P$1") (pintype "passive"))
      (node (ref "U4") (pin "3") (pinfunction "RFIN_3") (pintype "bidirectional"))
    )
    (net (code "34") (name "Net-(U4-VCC)") (class "Default")
      (node (ref "C12") (pin "2") (pinfunction "2_2") (pintype "passive"))
      (node (ref "C15") (pin "2") (pinfunction "2_2") (pintype "passive"))
      (node (ref "R5") (pin "2") (pinfunction "2_2") (pintype "passive"))
      (node (ref "U4") (pin "4") (pinfunction "VCC_4") (pintype "power_in"))
    )
    (net (code "35") (name "Net-(U4-~{SHDN})") (class "Default")
      (node (ref "R6") (pin "2") (pinfunction "2_2") (pintype "passive"))
      (node (ref "U4") (pin "5") (pinfunction "~{SHDN}_5") (pintype "bidirectional"))
    )
    (net (code "36") (name "Net-(U5-RESERVED)") (class "Default")
      (node (ref "R18") (pin "2") (pinfunction "2_2") (pintype "passive"))
      (node (ref "U5") (pin "16") (pinfunction "RESERVED_16") (pintype "bidirectional"))
    )
    (net (code "37") (name "Net-(U5-RESERVED1)") (class "Default")
      (node (ref "R19") (pin "2") (pinfunction "2_2") (pintype "passive"))
      (node (ref "U5") (pin "17") (pinfunction "RESERVED1_17") (pintype "bidirectional"))
    )
    (net (code "38") (name "Net-(U5-TXD1)") (class "Default")
      (node (ref "R38") (pin "1") (pinfunction "1_1") (pintype "passive"))
      (node (ref "U5") (pin "2") (pinfunction "TXD1_2") (pintype "bidirectional"))
    )
    (net (code "39") (name "Net-(U5-V_BCKP)") (class "Default")
      (node (ref "BAT1") (pin "+1") (pinfunction "V+_+1") (pintype "bidirectional"))
      (node (ref "BAT1") (pin "+2") (pinfunction "V+_+2") (pintype "bidirectional"))
      (node (ref "U5") (pin "6") (pinfunction "V_BCKP_6") (pintype "bidirectional"))
    )
    (net (code "40") (name "Net-(U7-SD3)") (class "Default")
      (node (ref "R35") (pin "2") (pinfunction "2_2") (pintype "passive"))
      (node (ref "U7") (pin "18") (pinfunction "SD3_18") (pintype "bidirectional"))
    )
    (net (code "41") (name "Net-(U7-TXD0)") (class "Default")
      (node (ref "R33") (pin "2") (pinfunction "2_2") (pintype "passive"))
      (node (ref "U7") (pin "35") (pinfunction "TXD0_35") (pintype "output"))
    )
    (net (code "42") (name "Net-(U9-RH1_OX)") (class "Default")
      (node (ref "R23") (pin "2") (pinfunction "2_2") (pintype "passive"))
      (node (ref "U9") (pin "A") (pinfunction "RH1_OX_A") (pintype "bidirectional"))
    )
    (net (code "43") (name "Net-(U9-RH1_RED)") (class "Default")
      (node (ref "R21") (pin "2") (pinfunction "2_2") (pintype "passive"))
      (node (ref "U9") (pin "C") (pinfunction "RH1_RED_C") (pintype "bidirectional"))
    )
    (net (code "44") (name "Net-(USB1-VBUS)") (class "Default")
      (node (ref "L3") (pin "1") (pinfunction "1_1") (pintype "passive"))
      (node (ref "USB1") (pin "1") (pinfunction "VBUS_1") (pintype "power_in"))
    )
    (net (code "45") (name "PM_RESET") (class "Default")
      (node (ref "U6") (pin "RESET") (pinfunction "RESET_RESET") (pintype "bidirectional"))
      (node (ref "U7") (pin "28") (pinfunction "IO17_28") (pintype "bidirectional"))
    )
    (net (code "46") (name "PM_SET") (class "Default")
      (node (ref "U6") (pin "SET") (pinfunction "SET_SET") (pintype "bidirectional"))
      (node (ref "U7") (pin "29") (pinfunction "IO5_29") (pintype "bidirectional"))
    )
    (net (code "47") (name "RELOAD") (class "Default")
      (node (ref "C4") (pin "2") (pinfunction "2_2") (pintype "passive"))
      (node (ref "RELOAD") (pin "2") (pinfunction "B0_2") (pintype "bidirectional"))
      (node (ref "U7") (pin "4") (pinfunction "IO36/SEN_VP/A1_0_4") (pintype "passive"))
    )
    (net (code "48") (name "RESET") (class "Default")
      (node (ref "C3") (pin "2") (pinfunction "2_2") (pintype "passive"))
      (node (ref "Q3") (pin "2") (pinfunction "E_2") (pintype "passive"))
      (node (ref "RESET") (pin "2") (pinfunction "B0_2") (pintype "bidirectional"))
      (node (ref "U7") (pin "3") (pinfunction "EN_3") (pintype "input"))
    )
    (net (code "49") (name "RF_IN") (class "Default")
      (node (ref "U4") (pin "6") (pinfunction "RFOUT_6") (pintype "bidirectional"))
      (node (ref "U5") (pin "11") (pinfunction "RF_IN_11") (pintype "bidirectional"))
    )
    (net (code "50") (name "RTS") (class "Default")
      (node (ref "Q3") (pin "3") (pinfunction "C_3") (pintype "passive"))
      (node (ref "R1") (pin "1") (pinfunction "1_1") (pintype "passive"))
      (node (ref "U2") (pin "16") (pinfunction "RTS#_16") (pintype "output"))
    )
    (net (code "51") (name "RXD0") (class "Default")
      (node (ref "R34") (pin "1") (pinfunction "1_1") (pintype "passive"))
      (node (ref "U7") (pin "34") (pinfunction "RXD0_34") (pintype "input"))
    )
    (net (code "52") (name "SCL") (class "Default")
      (node (ref "R22") (pin "1") (pinfunction "1_1") (pintype "passive"))
      (node (ref "U1") (pin "6") (pinfunction "SCL_6") (pintype "input"))
      (node (ref "U7") (pin "12") (pinfunction "IO27/A2_7_12") (pintype "bidirectional"))
    )
    (net (code "53") (name "SDA") (class "Default")
      (node (ref "R10") (pin "1") (pinfunction "1_1") (pintype "passive"))
      (node (ref "U1") (pin "1") (pinfunction "SDA_1") (pintype "bidirectional"))
      (node (ref "U7") (pin "11") (pinfunction "IO26/DAC2/A2_9_11") (pintype "bidirectional"))
    )
    (net (code "54") (name "SD_CLK_IO14") (class "Default")
      (node (ref "R15") (pin "1") (pinfunction "1_1") (pintype "passive"))
      (node (ref "SD1") (pin "5") (pinfunction "SCLK_5") (pintype "bidirectional"))
      (node (ref "U7") (pin "13") (pinfunction "IO14/A2_6_13") (pintype "bidirectional"))
    )
    (net (code "55") (name "SD_CMD_IO15") (class "Default")
      (node (ref "R17") (pin "1") (pinfunction "1_1") (pintype "passive"))
      (node (ref "SD1") (pin "3") (pinfunction "DI_3") (pintype "bidirectional"))
      (node (ref "U7") (pin "23") (pinfunction "IO15/A2_3_23") (pintype "bidirectional"))
    )
    (net (code "56") (name "SD_CS_IO13") (class "Default")
      (node (ref "R8") (pin "1") (pinfunction "1_1") (pintype "passive"))
      (node (ref "SD1") (pin "2") (pinfunction "CS_2") (pintype "bidirectional"))
      (node (ref "U7") (pin "16") (pinfunction "IO13/A2_4_16") (pintype "bidirectional"))
    )
    (net (code "57") (name "SD_D0_IO2") (class "Default")
      (node (ref "R12") (pin "2") (pinfunction "2_2") (pintype "passive"))
      (node (ref "R9") (pin "1") (pinfunction "1_1") (pintype "passive"))
      (node (ref "SD1") (pin "7") (pinfunction "DO_7") (pintype "bidirectional"))
      (node (ref "U7") (pin "24") (pinfunction "IO2/A2_2_24") (pintype "bidirectional"))
    )
    (net (code "58") (name "SD_D1_IO4") (class "Default")
      (node (ref "SD1") (pin "8") (pinfunction "DATA1_8") (pintype "bidirectional"))
      (node (ref "U7") (pin "26") (pinfunction "IO4/A2_0_26") (pintype "bidirectional"))
    )
    (net (code "59") (name "SD_D2_IO12") (class "Default")
      (node (ref "SD1") (pin "1") (pinfunction "DATA2_1") (pintype "bidirectional"))
      (node (ref "U7") (pin "14") (pinfunction "IO12/A2_5_14") (pintype "bidirectional"))
    )
    (net (code "60") (name "STANDBY") (class "Default")
      (node (ref "U5") (pin "5") (pinfunction "STANDBY_5") (pintype "bidirectional"))
      (node (ref "U7") (pin "36") (pinfunction "IO22_36") (pintype "bidirectional"))
    )
    (net (code "61") (name "STAT_LED1") (class "Default")
      (node (ref "R14") (pin "2") (pinfunction "2_2") (pintype "passive"))
      (node (ref "U7") (pin "33") (pinfunction "IO21_33") (pintype "bidirectional"))
    )
    (net (code "62") (name "STAT_LED2") (class "Default")
      (node (ref "R16") (pin "2") (pinfunction "2_2") (pintype "passive"))
      (node (ref "U7") (pin "31") (pinfunction "IO19_31") (pintype "bidirectional"))
    )
    (net (code "63") (name "STAT_LED3") (class "Default")
      (node (ref "R2") (pin "2") (pinfunction "2_2") (pintype "passive"))
      (node (ref "U7") (pin "30") (pinfunction "IO18_30") (pintype "bidirectional"))
    )
    (net (code "64") (name "TIMER") (class "Default")
      (node (ref "U5") (pin "18") (pinfunction "TIMER_18") (pintype "bidirectional"))
      (node (ref "U7") (pin "37") (pinfunction "IO23_37") (pintype "bidirectional"))
    )
    (net (code "65") (name "TXD0") (class "Default")
      (node (ref "R33") (pin "1") (pinfunction "1_1") (pintype "passive"))
      (node (ref "U2") (pin "4") (pinfunction "RXD_4") (pintype "input"))
    )
    (net (code "66") (name "U1RXD") (class "Default")
      (node (ref "R38") (pin "2") (pinfunction "2_2") (pintype "passive"))
      (node (ref "U7") (pin "17") (pinfunction "SD2_17") (pintype "bidirectional"))
    )
    (net (code "67") (name "U1TXD") (class "Default")
      (node (ref "R35") (pin "1") (pinfunction "1_1") (pintype "passive"))
      (node (ref "U5") (pin "3") (pinfunction "RXD1_3") (pintype "bidirectional"))
    )
    (net (code "68") (name "U2RXD") (class "Default")
      (node (ref "R37") (pin "1") (pinfunction "1_1") (pintype "passive"))
      (node (ref "U7") (pin "27") (pinfunction "IO16_27") (pintype "bidirectional"))
    )
    (net (code "69") (name "VCC_RF") (class "Default")
      (node (ref "R5") (pin "1") (pinfunction "1_1") (pintype "passive"))
      (node (ref "U5") (pin "14") (pinfunction "VCC_RF_14") (pintype "power_in"))
    )
    (net (code "70") (name "VOX_RAWA") (class "Default")
      (node (ref "R20") (pin "2") (pinfunction "2_2") (pintype "passive"))
      (node (ref "U8") (pin "3") (pinfunction "3_3") (pintype "bidirectional"))
      (node (ref "U9") (pin "B") (pinfunction "RS1_OX_B") (pintype "bidirectional"))
    )
    (net (code "71") (name "VOX_RAWB") (class "Default")
      (node (ref "U7") (pin "9") (pinfunction "IO33/A1_5/X32N_9") (pintype "bidirectional"))
      (node (ref "U8") (pin "1") (pinfunction "1_1") (pintype "bidirectional"))
      (node (ref "U8") (pin "2") (pinfunction "2_2") (pintype "bidirectional"))
    )
    (net (code "72") (name "VRED_RAWA") (class "Default")
      (node (ref "R11") (pin "2") (pinfunction "2_2") (pintype "passive"))
      (node (ref "U8") (pin "5") (pinfunction "5_5") (pintype "bidirectional"))
      (node (ref "U9") (pin "D") (pinfunction "RS1_RED_D") (pintype "bidirectional"))
    )
    (net (code "73") (name "VRED_RAWB") (class "Default")
      (node (ref "U7") (pin "10") (pinfunction "IO25/DAC1/A2_8_10") (pintype "bidirectional"))
      (node (ref "U8") (pin "6") (pinfunction "6_6") (pintype "bidirectional"))
      (node (ref "U8") (pin "7") (pinfunction "7_7") (pintype "bidirectional"))
    )
    (net (code "74") (name "unconnected-(C8-PadP$M)") (class "Default")
      (node (ref "C8") (pin "P$M") (pinfunction "P$M_P$M") (pintype "passive"))
    )
    (net (code "75") (name "unconnected-(C8-PadP$P)") (class "Default")
      (node (ref "C8") (pin "P$P") (pinfunction "P$P_P$P") (pintype "passive"))
    )
    (net (code "76") (name "unconnected-(J3-G+-Pad10)") (class "Default")
      (node (ref "J3") (pin "10") (pinfunction "G+_10") (pintype "bidirectional"))
    )
    (net (code "77") (name "unconnected-(J3-G--Pad9)") (class "Default")
      (node (ref "J3") (pin "9") (pinfunction "G-_9") (pintype "bidirectional"))
    )
    (net (code "78") (name "unconnected-(J3-Pad1)") (class "Default")
      (node (ref "J3") (pin "1") (pinfunction "1_1") (pintype "bidirectional"))
    )
    (net (code "79") (name "unconnected-(J3-Pad2)") (class "Default")
      (node (ref "J3") (pin "2") (pinfunction "2_2") (pintype "bidirectional"))
    )
    (net (code "80") (name "unconnected-(J3-Pad3)") (class "Default")
      (node (ref "J3") (pin "3") (pinfunction "3_3") (pintype "bidirectional"))
    )
    (net (code "81") (name "unconnected-(J3-Pad4)") (class "Default")
      (node (ref "J3") (pin "4") (pinfunction "4_4") (pintype "bidirectional"))
    )
    (net (code "82") (name "unconnected-(J3-Pad5)") (class "Default")
      (node (ref "J3") (pin "5") (pinfunction "5_5") (pintype "bidirectional"))
    )
    (net (code "83") (name "unconnected-(J3-Pad6)") (class "Default")
      (node (ref "J3") (pin "6") (pinfunction "6_6") (pintype "bidirectional"))
    )
    (net (code "84") (name "unconnected-(J3-Pad7)") (class "Default")
      (node (ref "J3") (pin "7") (pinfunction "7_7") (pintype "bidirectional"))
    )
    (net (code "85") (name "unconnected-(J3-Pad8)") (class "Default")
      (node (ref "J3") (pin "8") (pinfunction "8_8") (pintype "bidirectional"))
    )
    (net (code "86") (name "unconnected-(J3-Pad13)") (class "Default")
      (node (ref "J3") (pin "13") (pinfunction "13_13") (pintype "bidirectional"))
    )
    (net (code "87") (name "unconnected-(J3-Pad14)") (class "Default")
      (node (ref "J3") (pin "14") (pinfunction "14_14") (pintype "bidirectional"))
    )
    (net (code "88") (name "unconnected-(J3-Y+-Pad12)") (class "Default")
      (node (ref "J3") (pin "12") (pinfunction "Y+_12") (pintype "bidirectional"))
    )
    (net (code "89") (name "unconnected-(J3-Y--Pad11)") (class "Default")
      (node (ref "J3") (pin "11") (pinfunction "Y-_11") (pintype "bidirectional"))
    )
    (net (code "90") (name "unconnected-(SD1-CDN-Pad9)") (class "Default")
      (node (ref "SD1") (pin "9") (pinfunction "CDN_9") (pintype "bidirectional"))
    )
    (net (code "91") (name "unconnected-(U$1-Pad1)") (class "Default")
      (node (ref "U$1") (pin "1") (pinfunction "1_1") (pintype "bidirectional"))
    )
    (net (code "92") (name "unconnected-(U$1-Pad2)") (class "Default")
      (node (ref "U$1") (pin "2") (pinfunction "2_2") (pintype "bidirectional"))
    )
    (net (code "93") (name "unconnected-(U$1-Pad3)") (class "Default")
      (node (ref "U$1") (pin "3") (pinfunction "3_3") (pintype "bidirectional"))
    )
    (net (code "94") (name "unconnected-(U$1-Pad4)") (class "Default")
      (node (ref "U$1") (pin "4") (pinfunction "4_4") (pintype "bidirectional"))
    )
    (net (code "95") (name "unconnected-(U$1-Pad5)") (class "Default")
      (node (ref "U$1") (pin "5") (pinfunction "5_5") (pintype "bidirectional"))
    )
    (net (code "96") (name "unconnected-(U$1-Pad6)") (class "Default")
      (node (ref "U$1") (pin "6") (pinfunction "6_6") (pintype "bidirectional"))
    )
    (net (code "97") (name "unconnected-(U$1-Pad7)") (class "Default")
      (node (ref "U$1") (pin "7") (pinfunction "7_7") (pintype "bidirectional"))
    )
    (net (code "98") (name "unconnected-(U$1-Pad8)") (class "Default")
      (node (ref "U$1") (pin "8") (pinfunction "8_8") (pintype "bidirectional"))
    )
    (net (code "99") (name "unconnected-(U2-ACT#-Pad2)") (class "Default")
      (node (ref "U2") (pin "2") (pinfunction "ACT#_2") (pintype "output"))
    )
    (net (code "100") (name "unconnected-(U2-CKO-Pad1)") (class "Default")
      (node (ref "U2") (pin "1") (pinfunction "CKO_1") (pintype "output"))
    )
    (net (code "101") (name "unconnected-(U2-CTS#-Pad11)") (class "Default")
      (node (ref "U2") (pin "11") (pinfunction "CTS#_11") (pintype "input"))
    )
    (net (code "102") (name "unconnected-(U2-DCD#-Pad14)") (class "Default")
      (node (ref "U2") (pin "14") (pinfunction "DCD#_14") (pintype "input"))
    )
    (net (code "103") (name "unconnected-(U2-DSR#-Pad12)") (class "Default")
      (node (ref "U2") (pin "12") (pinfunction "DSR#_12") (pintype "input"))
    )
    (net (code "104") (name "unconnected-(U2-NC-Pad17)") (class "Default")
      (node (ref "U2") (pin "17") (pinfunction "NC_17") (pintype "no_connect"))
    )
    (net (code "105") (name "unconnected-(U2-R232-Pad18)") (class "Default")
      (node (ref "U2") (pin "18") (pinfunction "R232_18") (pintype "input"))
    )
    (net (code "106") (name "unconnected-(U2-RI#-Pad13)") (class "Default")
      (node (ref "U2") (pin "13") (pinfunction "RI#_13") (pintype "input"))
    )
    (net (code "107") (name "unconnected-(U5-NC-Pad7)") (class "Default")
      (node (ref "U5") (pin "7") (pinfunction "NC_7") (pintype "bidirectional"))
    )
    (net (code "108") (name "unconnected-(U5-NC-Pad15)") (class "Default")
      (node (ref "U5") (pin "15") (pinfunction "NC_15") (pintype "bidirectional"))
    )
    (net (code "109") (name "unconnected-(U6-PadRXD)") (class "Default")
      (node (ref "U6") (pin "RXD") (pinfunction "RXD_RXD") (pintype "bidirectional"))
    )
    (net (code "110") (name "unconnected-(U7-IO39{slash}SEN_VN{slash}A1_3-Pad5)") (class "Default")
      (node (ref "U7") (pin "5") (pinfunction "IO39/SEN_VN/A1_3_5") (pintype "passive"))
    )
    (net (code "111") (name "unconnected-(U10-+-Pad1)") (class "Default")
      (node (ref "U10") (pin "1") (pinfunction "+_1") (pintype "input"))
    )
    (net (code "112") (name "unconnected-(U10---Pad2)") (class "Default")
      (node (ref "U10") (pin "2") (pinfunction "-_2") (pintype "input"))
    )
    (net (code "113") (name "unconnected-(U10-1-Pad3)") (class "Default")
      (node (ref "U10") (pin "3") (pinfunction "1_3") (pintype "output"))
    )
    (net (code "114") (name "unconnected-(U10-2-Pad4)") (class "Default")
      (node (ref "U10") (pin "4") (pinfunction "2_4") (pintype "output"))
    )
    (net (code "115") (name "unconnected-(U11-+-Pad1)") (class "Default")
      (node (ref "U11") (pin "1") (pinfunction "+_1") (pintype "input"))
    )
    (net (code "116") (name "unconnected-(U11---Pad2)") (class "Default")
      (node (ref "U11") (pin "2") (pinfunction "-_2") (pintype "input"))
    )
    (net (code "117") (name "unconnected-(U11-1-Pad3)") (class "Default")
      (node (ref "U11") (pin "3") (pinfunction "1_3") (pintype "output"))
    )
    (net (code "118") (name "unconnected-(U11-2-Pad4)") (class "Default")
      (node (ref "U11") (pin "4") (pinfunction "2_4") (pintype "output"))
    )
    (net (code "119") (name "unconnected-(USB1-ID-Pad4)") (class "Default")
      (node (ref "USB1") (pin "4") (pinfunction "ID_4") (pintype "bidirectional"))
    )
  )
)
